# Interface_Section.net
KiCad netlist of a schematic drawn in Altium Designer
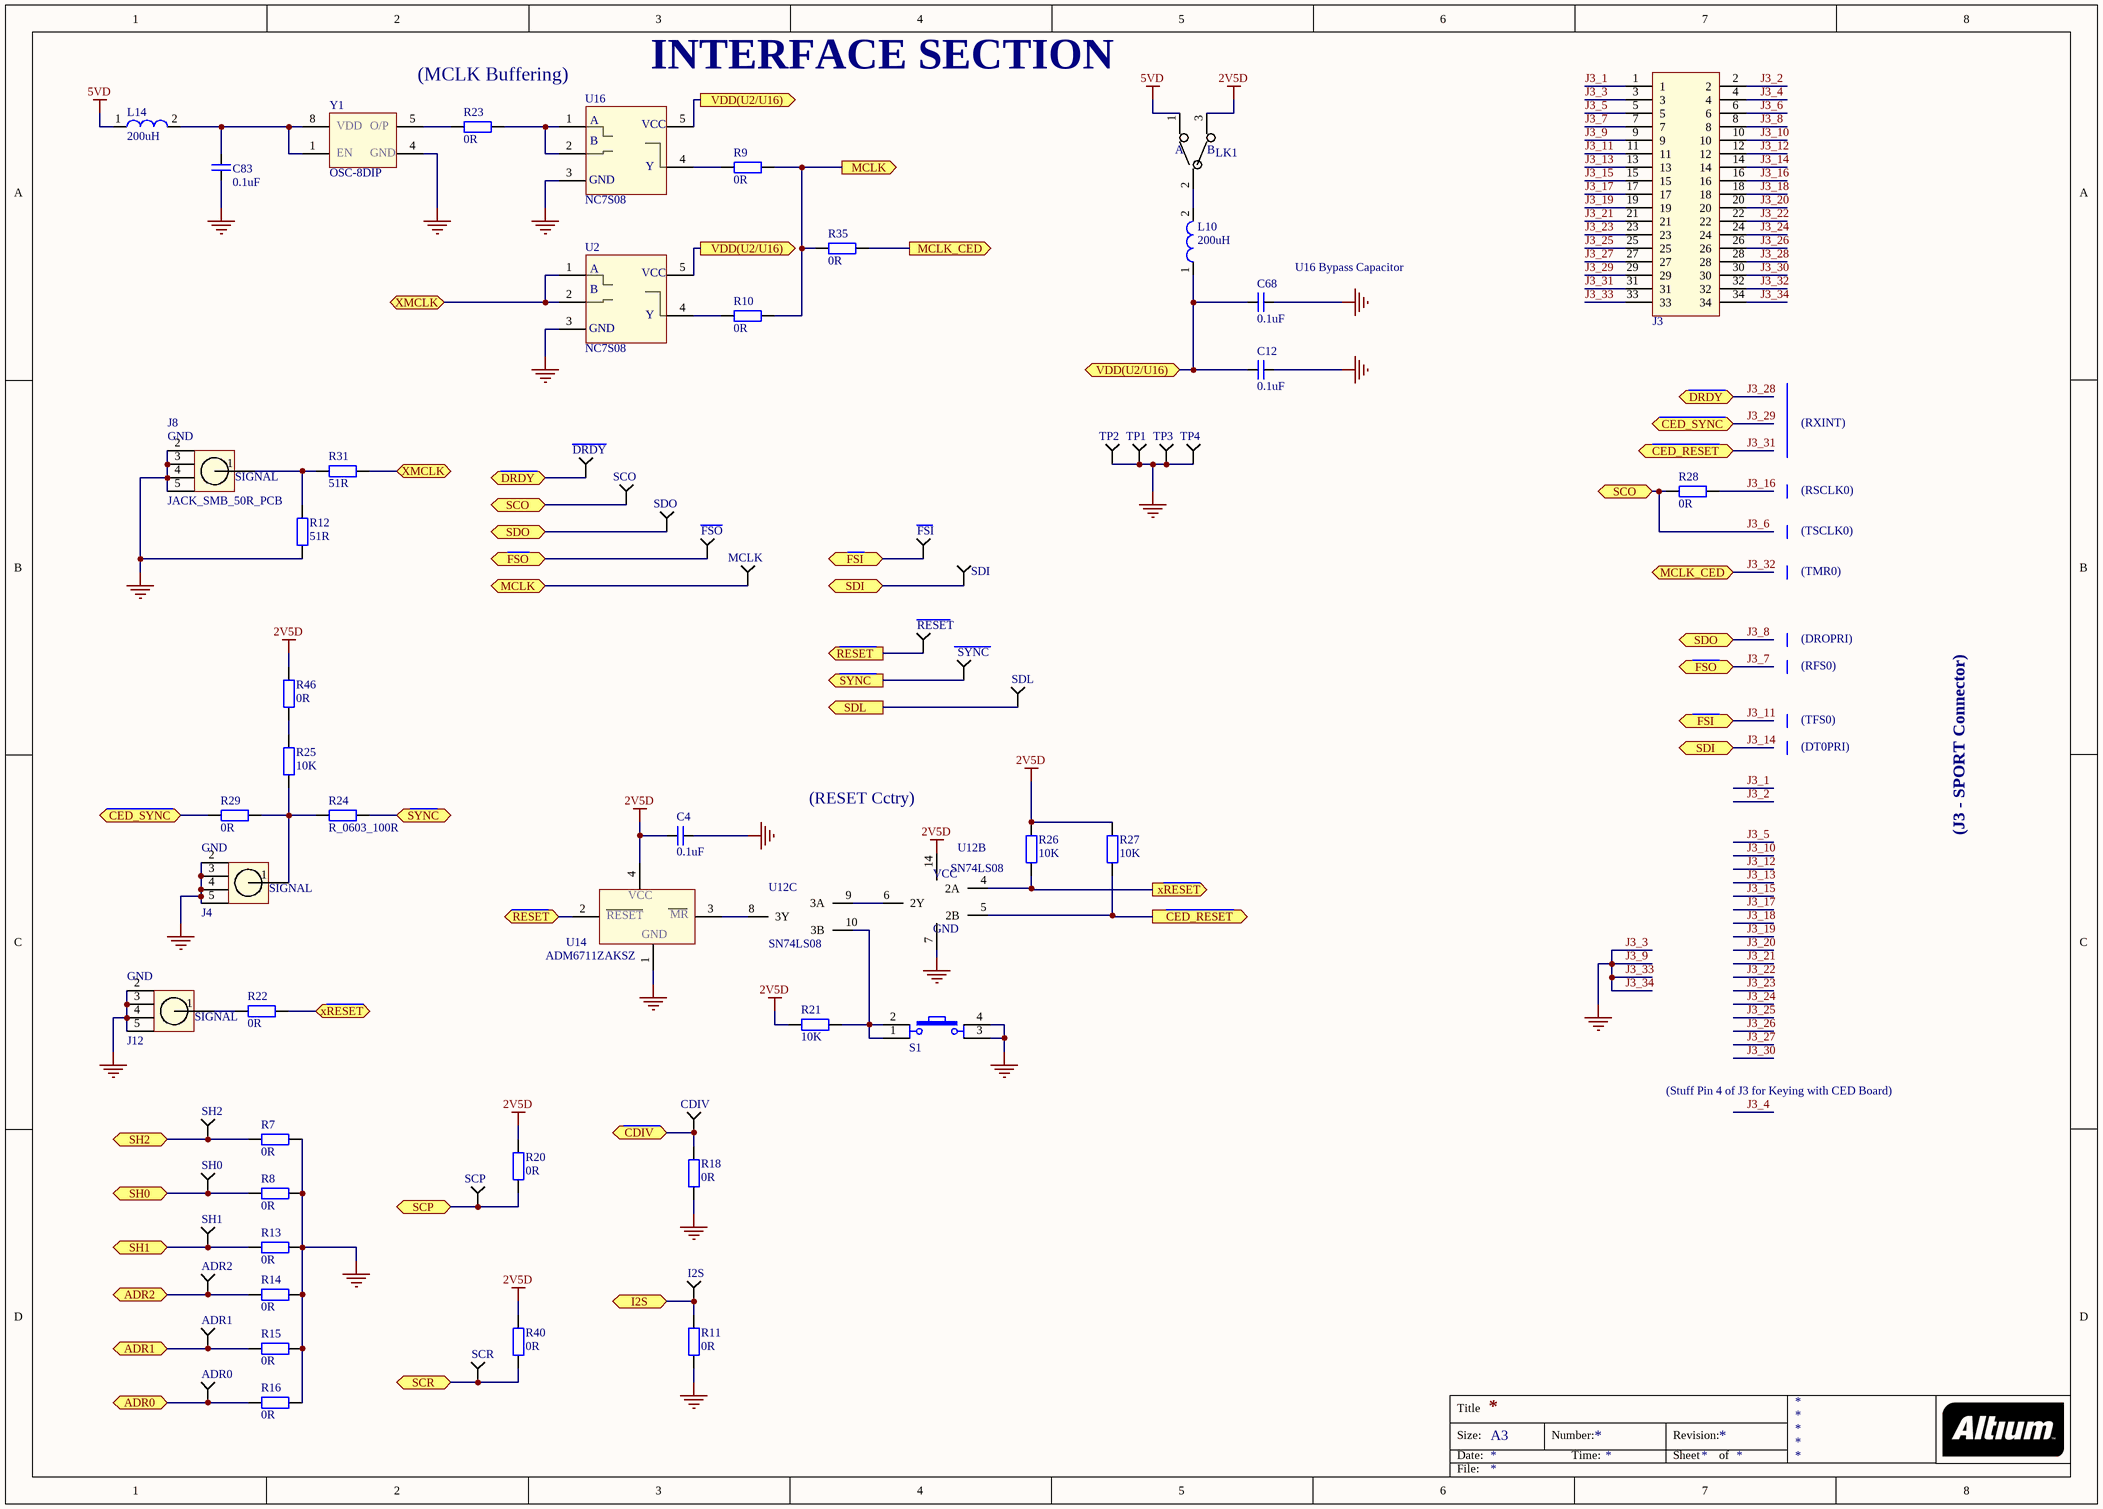
[diagram p0: Interface Section.SchDoc]

(export (version "E")
  (design (tool "Eeschema 10.0.6"))
  (components
    (comp (ref "ADR0")
      (value "Test point")
      (footprint "Test Point")
      (description "CONN HEADER VERT .100 1POS 30AU")
      (fields
        (field (name "MANUFACTURER") "TE Connectivity AMP Connectors")
        (field (name "MANUFACTURER PART NUMBER") "87220-1")
      )
      (libsource (lib "AD7763EDZ_Schematics Library") (part "Testpoint_PIN"))
    )
    (comp (ref "ADR1")
      (value "Test point")
      (footprint "Test Point")
      (description "CONN HEADER VERT .100 1POS 30AU")
      (fields
        (field (name "MANUFACTURER") "TE Connectivity AMP Connectors")
        (field (name "MANUFACTURER PART NUMBER") "87220-1")
      )
      (libsource (lib "AD7763EDZ_Schematics Library") (part "Testpoint_PIN"))
    )
    (comp (ref "ADR2")
      (value "Test point")
      (footprint "Test Point")
      (description "CONN HEADER VERT .100 1POS 30AU")
      (fields
        (field (name "MANUFACTURER") "TE Connectivity AMP Connectors")
        (field (name "MANUFACTURER PART NUMBER") "87220-1")
      )
      (libsource (lib "AD7763EDZ_Schematics Library") (part "Testpoint_PIN"))
    )
    (comp (ref "C4")
      (value "0.1uF")
      (footprint "C0603")
      (description "Ceramic Capacitor, 0.1 µF, ± 10%, X7R, 16 V, 0603")
      (fields
        (field (name "MANUFACTURER") "MULTICOMP")
        (field (name "MANUFACTURER PART NUMBER") "MCB0603R104KCT")
      )
      (libsource (lib "AD7763EDZ_Schematics Library") (part "C_0603_0.1uF"))
    )
    (comp (ref "C12")
      (value "0.1uF")
      (footprint "C0603")
      (description "Ceramic Capacitor, 0.1 µF, ± 10%, X7R, 16 V, 0603")
      (fields
        (field (name "MANUFACTURER") "MULTICOMP")
        (field (name "MANUFACTURER PART NUMBER") "MCB0603R104KCT")
      )
      (libsource (lib "AD7763EDZ_Schematics Library") (part "C_0603_0.1uF"))
    )
    (comp (ref "C68")
      (value "0.1uF")
      (footprint "C0603")
      (description "Ceramic Capacitor, 0.1 µF, ± 10%, X7R, 16 V, 0603")
      (fields
        (field (name "MANUFACTURER") "MULTICOMP")
        (field (name "MANUFACTURER PART NUMBER") "MCB0603R104KCT")
      )
      (libsource (lib "AD7763EDZ_Schematics Library") (part "C_0603_0.1uF"))
    )
    (comp (ref "C83")
      (value "0.1uF")
      (footprint "C0603")
      (description "Ceramic Capacitor, 0.1 µF, ± 10%, X7R, 16 V, 0603")
      (fields
        (field (name "MANUFACTURER") "MULTICOMP")
        (field (name "MANUFACTURER PART NUMBER") "MCB0603R104KCT")
      )
      (libsource (lib "AD7763EDZ_Schematics Library") (part "C_0603_0.1uF"))
    )
    (comp (ref "CDIV")
      (value "Test point")
      (footprint "Test Point")
      (description "CONN HEADER VERT .100 1POS 30AU")
      (fields
        (field (name "MANUFACTURER") "TE Connectivity AMP Connectors")
        (field (name "MANUFACTURER PART NUMBER") "87220-1")
      )
      (libsource (lib "AD7763EDZ_Schematics Library") (part "Testpoint_PIN"))
    )
    (comp (ref "DRDY")
      (value "Test point")
      (footprint "Test Point")
      (description "CONN HEADER VERT .100 1POS 30AU")
      (fields
        (field (name "MANUFACTURER") "TE Connectivity AMP Connectors")
        (field (name "MANUFACTURER PART NUMBER") "87220-1")
      )
      (libsource (lib "AD7763EDZ_Schematics Library") (part "Testpoint_PIN"))
    )
    (comp (ref "FSI")
      (value "Test point")
      (footprint "Test Point")
      (description "CONN HEADER VERT .100 1POS 30AU")
      (fields
        (field (name "MANUFACTURER") "TE Connectivity AMP Connectors")
        (field (name "MANUFACTURER PART NUMBER") "87220-1")
      )
      (libsource (lib "AD7763EDZ_Schematics Library") (part "Testpoint_PIN"))
    )
    (comp (ref "FSO")
      (value "Test point")
      (footprint "Test Point")
      (description "CONN HEADER VERT .100 1POS 30AU")
      (fields
        (field (name "MANUFACTURER") "TE Connectivity AMP Connectors")
        (field (name "MANUFACTURER PART NUMBER") "87220-1")
      )
      (libsource (lib "AD7763EDZ_Schematics Library") (part "Testpoint_PIN"))
    )
    (comp (ref "I2S")
      (value "Test point")
      (footprint "Test Point")
      (description "CONN HEADER VERT .100 1POS 30AU")
      (fields
        (field (name "MANUFACTURER") "TE Connectivity AMP Connectors")
        (field (name "MANUFACTURER PART NUMBER") "87220-1")
      )
      (libsource (lib "AD7763EDZ_Schematics Library") (part "Testpoint_PIN"))
    )
    (comp (ref "J3")
      (value "Female Header 17x2")
      (footprint "FM_Header_17x2_Bottom")
      (description "34pin 2.54mm DIL Vertical PC Tail Socket")
      (fields (field (name "MANUFACTURER") "Harwin") (field (name "MANUFACTURER PART NUMBER") "M20-7831746"))
      (libsource (lib "AD7763EDZ_Schematics Library") (part "Female header 17x2"))
    )
    (comp (ref "J4")
      (value "JACK_SMB_50R_PCB")
      (footprint "SMB Jack Radial")
      (description "CONN SMB JACK STR 50 OHM PCB")
      (fields (field (name "MANUFACTURER") "RADIALL") (field (name "MANUFACTURER PART NUMBER") "R114426000"))
      (libsource (lib "AD7763EDZ_Schematics Library") (part "JACK_SMB_50R_PCB"))
    )
    (comp (ref "J8")
      (value "JACK_SMB_50R_PCB")
      (footprint "SMB Jack Radial")
      (description "CONN SMB JACK STR 50 OHM PCB")
      (fields (field (name "MANUFACTURER") "RADIALL") (field (name "MANUFACTURER PART NUMBER") "R114426000"))
      (libsource (lib "AD7763EDZ_Schematics Library") (part "JACK_SMB_50R_PCB"))
    )
    (comp (ref "J12")
      (value "JACK_SMB_50R_PCB")
      (footprint "SMB Jack Radial")
      (description "CONN SMB JACK STR 50 OHM PCB")
      (fields (field (name "MANUFACTURER") "RADIALL") (field (name "MANUFACTURER PART NUMBER") "R114426000"))
      (libsource (lib "AD7763EDZ_Schematics Library") (part "JACK_SMB_50R_PCB"))
    )
    (comp (ref "L10")
      (value "200uH")
      (footprint "IND_0603")
      (description "FERRITE BEAD 1000 OHM 0.2A 0603")
      (fields
        (field (name "MANUFACTURER") "Wurth Electronics Inc")
        (field (name "MANUFACTURER PART NUMBER") "74279266")
      )
      (libsource (lib "AD7763EDZ_Schematics Library") (part "FERRITE_BEAT_200uH"))
    )
    (comp (ref "L14")
      (value "200uH")
      (footprint "IND_0603")
      (description "FERRITE BEAD 1000 OHM 0.2A 0603")
      (fields
        (field (name "MANUFACTURER") "Wurth Electronics Inc")
        (field (name "MANUFACTURER PART NUMBER") "74279266")
      )
      (libsource (lib "AD7763EDZ_Schematics Library") (part "FERRITE_BEAT_200uH"))
    )
    (comp (ref "LK1")
      (value "HEADER_3PIN_SIL")
      (footprint "M_Header_3")
      (description "SIL VERTICAL PC TAIL PIN HEADER 3PIN, M20-9990345")
      (fields
        (field (name "MANUFACTURER") "Harwin Inc")
        (field (name "MANUFACTURER PART NUMBER") "M20-9990345")
      )
      (libsource (lib "AD7763EDZ_Schematics Library") (part "HEADER_3PIN_SIL"))
    )
    (comp (ref "MCLK")
      (value "Test point")
      (footprint "Test Point")
      (description "CONN HEADER VERT .100 1POS 30AU")
      (fields
        (field (name "MANUFACTURER") "TE Connectivity AMP Connectors")
        (field (name "MANUFACTURER PART NUMBER") "87220-1")
      )
      (libsource (lib "AD7763EDZ_Schematics Library") (part "Testpoint_PIN"))
    )
    (comp (ref "R7")
      (value "0R")
      (footprint "R_0603")
      (description "RES SMD 0.0 OHM JUMPER 1/16W")
      (fields
        (field (name "MANUFACTURER") "TE Connectivity AMP Connectors")
        (field (name "MANUFACTURER PART NUMBER") "6-1622826-4")
      )
      (libsource (lib "AD7763EDZ_Schematics Library") (part "R_0603_0R"))
    )
    (comp (ref "R8")
      (value "0R")
      (footprint "R_0603")
      (description "RES SMD 0.0 OHM JUMPER 1/16W")
      (fields
        (field (name "MANUFACTURER") "TE Connectivity AMP Connectors")
        (field (name "MANUFACTURER PART NUMBER") "6-1622826-4")
      )
      (libsource (lib "AD7763EDZ_Schematics Library") (part "R_0603_0R"))
    )
    (comp (ref "R9")
      (value "0R")
      (footprint "R_0603")
      (description "RES SMD 0.0 OHM JUMPER 1/16W")
      (fields
        (field (name "MANUFACTURER") "TE Connectivity AMP Connectors")
        (field (name "MANUFACTURER PART NUMBER") "6-1622826-4")
      )
      (libsource (lib "AD7763EDZ_Schematics Library") (part "R_0603_0R"))
    )
    (comp (ref "R10")
      (value "0R")
      (footprint "R_0603")
      (description "RES SMD 0.0 OHM JUMPER 1/16W")
      (fields
        (field (name "MANUFACTURER") "TE Connectivity AMP Connectors")
        (field (name "MANUFACTURER PART NUMBER") "6-1622826-4")
      )
      (libsource (lib "AD7763EDZ_Schematics Library") (part "R_0603_0R"))
    )
    (comp (ref "R11")
      (value "0R")
      (footprint "R_0603")
      (description "RES SMD 0.0 OHM JUMPER 1/16W")
      (fields
        (field (name "MANUFACTURER") "TE Connectivity AMP Connectors")
        (field (name "MANUFACTURER PART NUMBER") "6-1622826-4")
      )
      (libsource (lib "AD7763EDZ_Schematics Library") (part "R_0603_0R"))
    )
    (comp (ref "R12")
      (value "51R")
      (footprint "R_0603")
      (description "RES SMD 51 OHM 1% 1/16W 0603")
      (fields
        (field (name "MANUFACTURER") "MULTICOMP")
        (field (name "MANUFACTURER PART NUMBER") "MC0063W0603151R")
      )
      (libsource (lib "AD7763EDZ_Schematics Library") (part "R_0603_51R"))
    )
    (comp (ref "R13")
      (value "0R")
      (footprint "R_0603")
      (description "RES SMD 0.0 OHM JUMPER 1/16W")
      (fields
        (field (name "MANUFACTURER") "TE Connectivity AMP Connectors")
        (field (name "MANUFACTURER PART NUMBER") "6-1622826-4")
      )
      (libsource (lib "AD7763EDZ_Schematics Library") (part "R_0603_0R"))
    )
    (comp (ref "R14")
      (value "0R")
      (footprint "R_0603")
      (description "RES SMD 0.0 OHM JUMPER 1/16W")
      (fields
        (field (name "MANUFACTURER") "TE Connectivity AMP Connectors")
        (field (name "MANUFACTURER PART NUMBER") "6-1622826-4")
      )
      (libsource (lib "AD7763EDZ_Schematics Library") (part "R_0603_0R"))
    )
    (comp (ref "R15")
      (value "0R")
      (footprint "R_0603")
      (description "RES SMD 0.0 OHM JUMPER 1/16W")
      (fields
        (field (name "MANUFACTURER") "TE Connectivity AMP Connectors")
        (field (name "MANUFACTURER PART NUMBER") "6-1622826-4")
      )
      (libsource (lib "AD7763EDZ_Schematics Library") (part "R_0603_0R"))
    )
    (comp (ref "R16")
      (value "0R")
      (footprint "R_0603")
      (description "RES SMD 0.0 OHM JUMPER 1/16W")
      (fields
        (field (name "MANUFACTURER") "TE Connectivity AMP Connectors")
        (field (name "MANUFACTURER PART NUMBER") "6-1622826-4")
      )
      (libsource (lib "AD7763EDZ_Schematics Library") (part "R_0603_0R"))
    )
    (comp (ref "R18")
      (value "0R")
      (footprint "R_0603")
      (description "RES SMD 0.0 OHM JUMPER 1/16W")
      (fields
        (field (name "MANUFACTURER") "TE Connectivity AMP Connectors")
        (field (name "MANUFACTURER PART NUMBER") "6-1622826-4")
      )
      (libsource (lib "AD7763EDZ_Schematics Library") (part "R_0603_0R"))
    )
    (comp (ref "R20")
      (value "0R")
      (footprint "R_0603")
      (description "RES SMD 0.0 OHM JUMPER 1/16W")
      (fields
        (field (name "MANUFACTURER") "TE Connectivity AMP Connectors")
        (field (name "MANUFACTURER PART NUMBER") "6-1622826-4")
      )
      (libsource (lib "AD7763EDZ_Schematics Library") (part "R_0603_0R"))
    )
    (comp (ref "R21")
      (value "10K")
      (footprint "R_0603")
      (description "RES SMD 10K OHM 1% 1/16W 0603")
      (fields
        (field (name "MANUFACTURER") "MULTICOMP")
        (field (name "MANUFACTURER PART NUMBER") "MC0063W0603110K")
      )
      (libsource (lib "AD7763EDZ_Schematics Library") (part "R_0603_10K"))
    )
    (comp (ref "R22")
      (value "0R")
      (footprint "R_0603")
      (description "RES SMD 0.0 OHM JUMPER 1/16W")
      (fields
        (field (name "MANUFACTURER") "TE Connectivity AMP Connectors")
        (field (name "MANUFACTURER PART NUMBER") "6-1622826-4")
      )
      (libsource (lib "AD7763EDZ_Schematics Library") (part "R_0603_0R"))
    )
    (comp (ref "R23")
      (value "0R")
      (footprint "R_0603")
      (description "RES SMD 0.0 OHM JUMPER 1/16W")
      (fields
        (field (name "MANUFACTURER") "TE Connectivity AMP Connectors")
        (field (name "MANUFACTURER PART NUMBER") "6-1622826-4")
      )
      (libsource (lib "AD7763EDZ_Schematics Library") (part "R_0603_0R"))
    )
    (comp (ref "R24")
      (value "R_0603_100R")
      (footprint "R_0603")
      (description "RES SMD 100 OHM 1% 1/10W 0603")
      (fields
        (field (name "MANUFACTURER") "Yageo")
        (field (name "MANUFACTURER PART NUMBER") "RC0603FR-07100RL")
      )
      (libsource (lib "AD7763") (part "R_0603_100R"))
    )
    (comp (ref "R25")
      (value "10K")
      (footprint "R_0603")
      (description "RES SMD 10K OHM 1% 1/16W 0603")
      (fields
        (field (name "MANUFACTURER") "MULTICOMP")
        (field (name "MANUFACTURER PART NUMBER") "MC0063W0603110K")
      )
      (libsource (lib "AD7763EDZ_Schematics Library") (part "R_0603_10K"))
    )
    (comp (ref "R26")
      (value "10K")
      (footprint "R_0603")
      (description "RES SMD 10K OHM 1% 1/16W 0603")
      (fields
        (field (name "MANUFACTURER") "MULTICOMP")
        (field (name "MANUFACTURER PART NUMBER") "MC0063W0603110K")
      )
      (libsource (lib "AD7763EDZ_Schematics Library") (part "R_0603_10K"))
    )
    (comp (ref "R27")
      (value "10K")
      (footprint "R_0603")
      (description "RES SMD 10K OHM 1% 1/16W 0603")
      (fields
        (field (name "MANUFACTURER") "MULTICOMP")
        (field (name "MANUFACTURER PART NUMBER") "MC0063W0603110K")
      )
      (libsource (lib "AD7763EDZ_Schematics Library") (part "R_0603_10K"))
    )
    (comp (ref "R28")
      (value "0R")
      (footprint "R_0603")
      (description "RES SMD 0.0 OHM JUMPER 1/16W")
      (fields
        (field (name "MANUFACTURER") "TE Connectivity AMP Connectors")
        (field (name "MANUFACTURER PART NUMBER") "6-1622826-4")
      )
      (libsource (lib "AD7763EDZ_Schematics Library") (part "R_0603_0R"))
    )
    (comp (ref "R29")
      (value "0R")
      (footprint "R_0603")
      (description "RES SMD 0.0 OHM JUMPER 1/16W")
      (fields
        (field (name "MANUFACTURER") "TE Connectivity AMP Connectors")
        (field (name "MANUFACTURER PART NUMBER") "6-1622826-4")
      )
      (libsource (lib "AD7763EDZ_Schematics Library") (part "R_0603_0R"))
    )
    (comp (ref "R31")
      (value "51R")
      (footprint "R_0603")
      (description "RES SMD 51 OHM 1% 1/16W 0603")
      (fields
        (field (name "MANUFACTURER") "MULTICOMP")
        (field (name "MANUFACTURER PART NUMBER") "MC0063W0603151R")
      )
      (libsource (lib "AD7763EDZ_Schematics Library") (part "R_0603_51R"))
    )
    (comp (ref "R35")
      (value "0R")
      (footprint "R_0603")
      (description "RES SMD 0.0 OHM JUMPER 1/16W")
      (fields
        (field (name "MANUFACTURER") "TE Connectivity AMP Connectors")
        (field (name "MANUFACTURER PART NUMBER") "6-1622826-4")
      )
      (libsource (lib "AD7763EDZ_Schematics Library") (part "R_0603_0R"))
    )
    (comp (ref "R40")
      (value "0R")
      (footprint "R_0603")
      (description "RES SMD 0.0 OHM JUMPER 1/16W")
      (fields
        (field (name "MANUFACTURER") "TE Connectivity AMP Connectors")
        (field (name "MANUFACTURER PART NUMBER") "6-1622826-4")
      )
      (libsource (lib "AD7763EDZ_Schematics Library") (part "R_0603_0R"))
    )
    (comp (ref "R46")
      (value "0R")
      (footprint "R_0603")
      (description "RES SMD 0.0 OHM JUMPER 1/16W")
      (fields
        (field (name "MANUFACTURER") "TE Connectivity AMP Connectors")
        (field (name "MANUFACTURER PART NUMBER") "6-1622826-4")
      )
      (libsource (lib "AD7763EDZ_Schematics Library") (part "R_0603_0R"))
    )
    (comp (ref "RESET")
      (value "Test point")
      (footprint "Test Point")
      (description "CONN HEADER VERT .100 1POS 30AU")
      (fields
        (field (name "MANUFACTURER") "TE Connectivity AMP Connectors")
        (field (name "MANUFACTURER PART NUMBER") "87220-1")
      )
      (libsource (lib "AD7763EDZ_Schematics Library") (part "Testpoint_PIN"))
    )
    (comp (ref "S1")
      (value "B3S-1000")
      (footprint "B3S-1000")
      (description "SWITCH TACTILE SPST-NO 0.05A 24V")
      (fields (field (name "MANUFACTURER") "Omron Electronics Inc-EMC Div"))
      (libsource (lib "AD7763EDZ_Schematics Library") (part "PUSH_BUTTON_SWITCH"))
    )
    (comp (ref "SCO")
      (value "Test point")
      (footprint "Test Point")
      (description "CONN HEADER VERT .100 1POS 30AU")
      (fields
        (field (name "MANUFACTURER") "TE Connectivity AMP Connectors")
        (field (name "MANUFACTURER PART NUMBER") "87220-1")
      )
      (libsource (lib "AD7763EDZ_Schematics Library") (part "Testpoint_PIN"))
    )
    (comp (ref "SCP")
      (value "Test point")
      (footprint "Test Point")
      (description "CONN HEADER VERT .100 1POS 30AU")
      (fields
        (field (name "MANUFACTURER") "TE Connectivity AMP Connectors")
        (field (name "MANUFACTURER PART NUMBER") "87220-1")
      )
      (libsource (lib "AD7763EDZ_Schematics Library") (part "Testpoint_PIN"))
    )
    (comp (ref "SCR")
      (value "Test point")
      (footprint "Test Point")
      (description "CONN HEADER VERT .100 1POS 30AU")
      (fields
        (field (name "MANUFACTURER") "TE Connectivity AMP Connectors")
        (field (name "MANUFACTURER PART NUMBER") "87220-1")
      )
      (libsource (lib "AD7763EDZ_Schematics Library") (part "Testpoint_PIN"))
    )
    (comp (ref "SDI")
      (value "Test point")
      (footprint "Test Point")
      (description "CONN HEADER VERT .100 1POS 30AU")
      (fields
        (field (name "MANUFACTURER") "TE Connectivity AMP Connectors")
        (field (name "MANUFACTURER PART NUMBER") "87220-1")
      )
      (libsource (lib "AD7763EDZ_Schematics Library") (part "Testpoint_PIN"))
    )
    (comp (ref "SDL")
      (value "Test point")
      (footprint "Test Point")
      (description "CONN HEADER VERT .100 1POS 30AU")
      (fields
        (field (name "MANUFACTURER") "TE Connectivity AMP Connectors")
        (field (name "MANUFACTURER PART NUMBER") "87220-1")
      )
      (libsource (lib "AD7763EDZ_Schematics Library") (part "Testpoint_PIN"))
    )
    (comp (ref "SDO")
      (value "Test point")
      (footprint "Test Point")
      (description "CONN HEADER VERT .100 1POS 30AU")
      (fields
        (field (name "MANUFACTURER") "TE Connectivity AMP Connectors")
        (field (name "MANUFACTURER PART NUMBER") "87220-1")
      )
      (libsource (lib "AD7763EDZ_Schematics Library") (part "Testpoint_PIN"))
    )
    (comp (ref "SH0")
      (value "Test point")
      (footprint "Test Point")
      (description "CONN HEADER VERT .100 1POS 30AU")
      (fields
        (field (name "MANUFACTURER") "TE Connectivity AMP Connectors")
        (field (name "MANUFACTURER PART NUMBER") "87220-1")
      )
      (libsource (lib "AD7763EDZ_Schematics Library") (part "Testpoint_PIN"))
    )
    (comp (ref "SH1")
      (value "Test point")
      (footprint "Test Point")
      (description "CONN HEADER VERT .100 1POS 30AU")
      (fields
        (field (name "MANUFACTURER") "TE Connectivity AMP Connectors")
        (field (name "MANUFACTURER PART NUMBER") "87220-1")
      )
      (libsource (lib "AD7763EDZ_Schematics Library") (part "Testpoint_PIN"))
    )
    (comp (ref "SH2")
      (value "Test point")
      (footprint "Test Point")
      (description "CONN HEADER VERT .100 1POS 30AU")
      (fields
        (field (name "MANUFACTURER") "TE Connectivity AMP Connectors")
        (field (name "MANUFACTURER PART NUMBER") "87220-1")
      )
      (libsource (lib "AD7763EDZ_Schematics Library") (part "Testpoint_PIN"))
    )
    (comp (ref "SYNC")
      (value "Test point")
      (footprint "Test Point")
      (description "CONN HEADER VERT .100 1POS 30AU")
      (fields
        (field (name "MANUFACTURER") "TE Connectivity AMP Connectors")
        (field (name "MANUFACTURER PART NUMBER") "87220-1")
      )
      (libsource (lib "AD7763EDZ_Schematics Library") (part "Testpoint_PIN"))
    )
    (comp (ref "TP1")
      (value "Test point")
      (footprint "Test Point")
      (description "CONN HEADER VERT .100 1POS 30AU")
      (fields
        (field (name "MANUFACTURER") "TE Connectivity AMP Connectors")
        (field (name "MANUFACTURER PART NUMBER") "87220-1")
      )
      (libsource (lib "AD7763EDZ_Schematics Library") (part "Testpoint_PIN"))
    )
    (comp (ref "TP2")
      (value "Test point")
      (footprint "Test Point")
      (description "CONN HEADER VERT .100 1POS 30AU")
      (fields
        (field (name "MANUFACTURER") "TE Connectivity AMP Connectors")
        (field (name "MANUFACTURER PART NUMBER") "87220-1")
      )
      (libsource (lib "AD7763EDZ_Schematics Library") (part "Testpoint_PIN"))
    )
    (comp (ref "TP3")
      (value "Test point")
      (footprint "Test Point")
      (description "CONN HEADER VERT .100 1POS 30AU")
      (fields
        (field (name "MANUFACTURER") "TE Connectivity AMP Connectors")
        (field (name "MANUFACTURER PART NUMBER") "87220-1")
      )
      (libsource (lib "AD7763EDZ_Schematics Library") (part "Testpoint_PIN"))
    )
    (comp (ref "TP4")
      (value "Test point")
      (footprint "Test Point")
      (description "CONN HEADER VERT .100 1POS 30AU")
      (fields
        (field (name "MANUFACTURER") "TE Connectivity AMP Connectors")
        (field (name "MANUFACTURER PART NUMBER") "87220-1")
      )
      (libsource (lib "AD7763EDZ_Schematics Library") (part "Testpoint_PIN"))
    )
    (comp (ref "U2")
      (value "NC7S08")
      (footprint "SOT23-5")
      (description "IC GATE AND 1CH 2-INP SOT-23-5")
      (fields
        (field (name "MANUFACTURER") "Fairchild Semiconductor")
        (field (name "MANUFACTURER PART NUMBER") "NC7SZ08M5")
      )
      (libsource (lib "AD7763EDZ_Schematics Library") (part "NC7S08"))
    )
    (comp (ref "U12")
      (value "SN74LS08")
      (footprint "TSSOP-14")
      (description "IC GATE AND 4CH 2-INP 14-TSSOP")
      (fields
        (field (name "MANUFACTURER") "Texas Instruments")
        (field (name "MANUFACTURER PART NUMBER") "SN74LVC08APWR")
      )
      (libsource (lib "AD7763") (part "74LS08"))
    )
    (comp (ref "U14")
      (value "ADM6711ZAKSZ")
      (footprint "SC70-4")
      (description "IC SUPERVISOR MPU 2.32V SC70-4")
      (fields
        (field (name "MANUFACTURER") "Analog Devices Inc")
        (field (name "MANUFACTURER PART NUMBER") "ADM6711ZAKSZ-REEL7")
      )
      (libsource (lib "AD7763EDZ_Schematics Library") (part "ADM6711"))
    )
    (comp (ref "U16")
      (value "NC7S08")
      (footprint "SOT23-5")
      (description "IC GATE AND 1CH 2-INP SOT-23-5")
      (fields
        (field (name "MANUFACTURER") "Fairchild Semiconductor")
        (field (name "MANUFACTURER PART NUMBER") "NC7SZ08M5")
      )
      (libsource (lib "AD7763EDZ_Schematics Library") (part "NC7S08"))
    )
    (comp (ref "Y1")
      (value "OSC-8DIP")
      (footprint "MXO45HS40M")
      (description "OSC XO 40.000MHZ HCMOS TTL PIN")
      (fields
        (field (name "MANUFACTURER") "CTS-Frequency Controls")
        (field (name "MANUFACTURER PART NUMBER") "MXO45HS-2C-40M0000")
      )
      (libsource (lib "AD7763EDZ_Schematics Library") (part "OSC-8DIP"))
    )
  )
  (nets
    (net (code "1") (name "/ADR0") (class "Default")
      (node (ref "ADR0") (pin "1") (pinfunction "1_1") (pintype "passive"))
      (node (ref "R16") (pin "1") (pinfunction "1_1") (pintype "passive"))
    )
    (net (code "2") (name "/ADR1") (class "Default")
      (node (ref "ADR1") (pin "1") (pinfunction "1_1") (pintype "passive"))
      (node (ref "R15") (pin "1") (pinfunction "1_1") (pintype "passive"))
    )
    (net (code "3") (name "/ADR2") (class "Default")
      (node (ref "ADR2") (pin "1") (pinfunction "1_1") (pintype "passive"))
      (node (ref "R14") (pin "1") (pinfunction "1_1") (pintype "passive"))
    )
    (net (code "4") (name "/CDIV") (class "Default")
      (node (ref "CDIV") (pin "1") (pinfunction "1_1") (pintype "passive"))
      (node (ref "R18") (pin "2") (pinfunction "2_2") (pintype "passive"))
    )
    (net (code "5") (name "/I2S") (class "Default")
      (node (ref "I2S") (pin "1") (pinfunction "1_1") (pintype "passive"))
      (node (ref "R11") (pin "2") (pinfunction "2_2") (pintype "passive"))
    )
    (net (code "6") (name "/J3_1") (class "Default")
      (node (ref "J3") (pin "1") (pinfunction "1_1") (pintype "passive"))
    )
    (net (code "7") (name "/J3_2") (class "Default")
      (node (ref "J3") (pin "2") (pinfunction "2_2") (pintype "passive"))
    )
    (net (code "8") (name "/J3_4") (class "Default")
      (node (ref "J3") (pin "4") (pinfunction "4_4") (pintype "passive"))
    )
    (net (code "9") (name "/J3_5") (class "Default")
      (node (ref "J3") (pin "5") (pinfunction "5_5") (pintype "passive"))
    )
    (net (code "10") (name "/J3_6") (class "Default")
      (node (ref "J3") (pin "6") (pinfunction "6_6") (pintype "passive"))
      (node (ref "R28") (pin "1") (pinfunction "1_1") (pintype "passive"))
      (node (ref "SCO") (pin "1") (pinfunction "1_1") (pintype "passive"))
    )
    (net (code "11") (name "/J3_7") (class "Default")
      (node (ref "FSO") (pin "1") (pinfunction "1_1") (pintype "passive"))
      (node (ref "J3") (pin "7") (pinfunction "7_7") (pintype "passive"))
    )
    (net (code "12") (name "/J3_8") (class "Default")
      (node (ref "J3") (pin "8") (pinfunction "8_8") (pintype "passive"))
      (node (ref "SDO") (pin "1") (pinfunction "1_1") (pintype "passive"))
    )
    (net (code "13") (name "/J3_10") (class "Default")
      (node (ref "J3") (pin "10") (pinfunction "10_10") (pintype "passive"))
    )
    (net (code "14") (name "/J3_11") (class "Default")
      (node (ref "FSI") (pin "1") (pinfunction "1_1") (pintype "passive"))
      (node (ref "J3") (pin "11") (pinfunction "11_11") (pintype "passive"))
    )
    (net (code "15") (name "/J3_12") (class "Default")
      (node (ref "J3") (pin "12") (pinfunction "12_12") (pintype "passive"))
    )
    (net (code "16") (name "/J3_13") (class "Default")
      (node (ref "J3") (pin "13") (pinfunction "13_13") (pintype "passive"))
    )
    (net (code "17") (name "/J3_14") (class "Default")
      (node (ref "J3") (pin "14") (pinfunction "14_14") (pintype "passive"))
      (node (ref "SDI") (pin "1") (pinfunction "1_1") (pintype "passive"))
    )
    (net (code "18") (name "/J3_15") (class "Default")
      (node (ref "J3") (pin "15") (pinfunction "15_15") (pintype "passive"))
    )
    (net (code "19") (name "/J3_16") (class "Default")
      (node (ref "J3") (pin "16") (pinfunction "16_16") (pintype "passive"))
      (node (ref "R28") (pin "2") (pinfunction "2_2") (pintype "passive"))
    )
    (net (code "20") (name "/J3_17") (class "Default")
      (node (ref "J3") (pin "17") (pinfunction "17_17") (pintype "passive"))
    )
    (net (code "21") (name "/J3_18") (class "Default")
      (node (ref "J3") (pin "18") (pinfunction "18_18") (pintype "passive"))
    )
    (net (code "22") (name "/J3_19") (class "Default")
      (node (ref "J3") (pin "19") (pinfunction "19_19") (pintype "passive"))
    )
    (net (code "23") (name "/J3_20") (class "Default")
      (node (ref "J3") (pin "20") (pinfunction "20_20") (pintype "passive"))
    )
    (net (code "24") (name "/J3_21") (class "Default")
      (node (ref "J3") (pin "21") (pinfunction "21_21") (pintype "passive"))
    )
    (net (code "25") (name "/J3_22") (class "Default")
      (node (ref "J3") (pin "22") (pinfunction "22_22") (pintype "passive"))
    )
    (net (code "26") (name "/J3_23") (class "Default")
      (node (ref "J3") (pin "23") (pinfunction "23_23") (pintype "passive"))
    )
    (net (code "27") (name "/J3_24") (class "Default")
      (node (ref "J3") (pin "24") (pinfunction "24_24") (pintype "passive"))
    )
    (net (code "28") (name "/J3_25") (class "Default")
      (node (ref "J3") (pin "25") (pinfunction "25_25") (pintype "passive"))
    )
    (net (code "29") (name "/J3_26") (class "Default")
      (node (ref "J3") (pin "26") (pinfunction "26_26") (pintype "passive"))
    )
    (net (code "30") (name "/J3_27") (class "Default")
      (node (ref "J3") (pin "27") (pinfunction "27_27") (pintype "passive"))
    )
    (net (code "31") (name "/J3_28") (class "Default")
      (node (ref "DRDY") (pin "1") (pinfunction "1_1") (pintype "passive"))
      (node (ref "J3") (pin "28") (pinfunction "28_28") (pintype "passive"))
    )
    (net (code "32") (name "/J3_29") (class "Default")
      (node (ref "J3") (pin "29") (pinfunction "29_29") (pintype "passive"))
      (node (ref "R29") (pin "2") (pinfunction "2_2") (pintype "passive"))
    )
    (net (code "33") (name "/J3_30") (class "Default")
      (node (ref "J3") (pin "30") (pinfunction "30_30") (pintype "passive"))
    )
    (net (code "34") (name "/J3_31") (class "Default")
      (node (ref "J3") (pin "31") (pinfunction "31_31") (pintype "passive"))
      (node (ref "R27") (pin "1") (pinfunction "1_1") (pintype "passive"))
      (node (ref "U12") (pin "5") (pinfunction "2B_5") (pintype "passive"))
    )
    (net (code "35") (name "/J3_32") (class "Default")
      (node (ref "J3") (pin "32") (pinfunction "32_32") (pintype "passive"))
      (node (ref "R35") (pin "2") (pinfunction "2_2") (pintype "passive"))
    )
    (net (code "36") (name "/MCLK") (class "Default")
      (node (ref "MCLK") (pin "1") (pinfunction "1_1") (pintype "passive"))
      (node (ref "R10") (pin "2") (pinfunction "2_2") (pintype "passive"))
      (node (ref "R35") (pin "1") (pinfunction "1_1") (pintype "passive"))
      (node (ref "R9") (pin "2") (pinfunction "2_2") (pintype "passive"))
    )
    (net (code "37") (name "/RESET") (class "Default")
      (node (ref "RESET") (pin "1") (pinfunction "1_1") (pintype "passive"))
      (node (ref "U14") (pin "2") (pinfunction "RESET_2") (pintype "passive"))
    )
    (net (code "38") (name "/SCP") (class "Default")
      (node (ref "R20") (pin "1") (pinfunction "1_1") (pintype "passive"))
      (node (ref "SCP") (pin "1") (pinfunction "1_1") (pintype "passive"))
    )
    (net (code "39") (name "/SCR") (class "Default")
      (node (ref "R40") (pin "1") (pinfunction "1_1") (pintype "passive"))
      (node (ref "SCR") (pin "1") (pinfunction "1_1") (pintype "passive"))
    )
    (net (code "40") (name "/SDL") (class "Default")
      (node (ref "SDL") (pin "1") (pinfunction "1_1") (pintype "passive"))
    )
    (net (code "41") (name "/SH0") (class "Default")
      (node (ref "R8") (pin "1") (pinfunction "1_1") (pintype "passive"))
      (node (ref "SH0") (pin "1") (pinfunction "1_1") (pintype "passive"))
    )
    (net (code "42") (name "/SH1") (class "Default")
      (node (ref "R13") (pin "1") (pinfunction "1_1") (pintype "passive"))
      (node (ref "SH1") (pin "1") (pinfunction "1_1") (pintype "passive"))
    )
    (net (code "43") (name "/SH2") (class "Default")
      (node (ref "R7") (pin "1") (pinfunction "1_1") (pintype "passive"))
      (node (ref "SH2") (pin "1") (pinfunction "1_1") (pintype "passive"))
    )
    (net (code "44") (name "/SYNC") (class "Default")
      (node (ref "R24") (pin "2") (pinfunction "2_2") (pintype "passive"))
      (node (ref "SYNC") (pin "1") (pinfunction "1_1") (pintype "passive"))
    )
    (net (code "45") (name "/VDD(U2{slash}U16)") (class "Default")
      (node (ref "C12") (pin "1") (pinfunction "1_1") (pintype "passive"))
      (node (ref "C68") (pin "1") (pinfunction "1_1") (pintype "passive"))
      (node (ref "L10") (pin "1") (pinfunction "1_1") (pintype "passive"))
      (node (ref "U16") (pin "5") (pinfunction "VCC_5") (pintype "passive"))
      (node (ref "U2") (pin "5") (pinfunction "VCC_5") (pintype "passive"))
    )
    (net (code "46") (name "/XMCLK") (class "Default")
      (node (ref "R31") (pin "2") (pinfunction "2_2") (pintype "passive"))
      (node (ref "U2") (pin "1") (pinfunction "A_1") (pintype "passive"))
      (node (ref "U2") (pin "2") (pinfunction "B_2") (pintype "passive"))
    )
    (net (code "47") (name "/xRESET") (class "Default")
      (node (ref "R22") (pin "2") (pinfunction "2_2") (pintype "passive"))
      (node (ref "R26") (pin "1") (pinfunction "1_1") (pintype "passive"))
      (node (ref "U12") (pin "4") (pinfunction "2A_4") (pintype "passive"))
    )
    (net (code "48") (name "2V5D") (class "Default")
      (node (ref "C4") (pin "1") (pinfunction "1_1") (pintype "passive"))
      (node (ref "LK1") (pin "3") (pinfunction "3_3") (pintype "passive"))
      (node (ref "R20") (pin "2") (pinfunction "2_2") (pintype "passive"))
      (node (ref "R21") (pin "1") (pinfunction "1_1") (pintype "passive"))
      (node (ref "R26") (pin "2") (pinfunction "2_2") (pintype "passive"))
      (node (ref "R27") (pin "2") (pinfunction "2_2") (pintype "passive"))
      (node (ref "R40") (pin "2") (pinfunction "2_2") (pintype "passive"))
      (node (ref "R46") (pin "2") (pinfunction "2_2") (pintype "passive"))
      (node (ref "U12") (pin "14") (pinfunction "VCC_14") (pintype "power_in"))
      (node (ref "U14") (pin "4") (pinfunction "RESET_4") (pintype "passive"))
    )
    (net (code "49") (name "5VD") (class "Default")
      (node (ref "L14") (pin "1") (pinfunction "1_1") (pintype "passive"))
      (node (ref "LK1") (pin "1") (pinfunction "1_1") (pintype "passive"))
    )
    (net (code "50") (name "<NO NET>") (class "Default")
      (node (ref "C12") (pin "2") (pinfunction "2_2") (pintype "passive"))
      (node (ref "C4") (pin "2") (pinfunction "2_2") (pintype "passive"))
      (node (ref "C68") (pin "2") (pinfunction "2_2") (pintype "passive"))
      (node (ref "C83") (pin "1") (pinfunction "1_1") (pintype "passive"))
      (node (ref "J12") (pin "2") (pinfunction "2_2") (pintype "power_in"))
      (node (ref "J12") (pin "3") (pinfunction "3_3") (pintype "power_in"))
      (node (ref "J12") (pin "4") (pinfunction "4_4") (pintype "power_in"))
      (node (ref "J12") (pin "5") (pinfunction "5_5") (pintype "power_in"))
      (node (ref "J3") (pin "3") (pinfunction "3_3") (pintype "passive"))
      (node (ref "J3") (pin "33") (pinfunction "33_33") (pintype "passive"))
      (node (ref "J3") (pin "34") (pinfunction "34_34") (pintype "passive"))
      (node (ref "J3") (pin "9") (pinfunction "9_9") (pintype "passive"))
      (node (ref "J4") (pin "2") (pinfunction "2_2") (pintype "power_in"))
      (node (ref "J4") (pin "3") (pinfunction "3_3") (pintype "power_in"))
      (node (ref "J4") (pin "4") (pinfunction "4_4") (pintype "power_in"))
      (node (ref "J4") (pin "5") (pinfunction "5_5") (pintype "power_in"))
      (node (ref "J8") (pin "2") (pinfunction "2_2") (pintype "power_in"))
      (node (ref "J8") (pin "3") (pinfunction "3_3") (pintype "power_in"))
      (node (ref "J8") (pin "4") (pinfunction "4_4") (pintype "power_in"))
      (node (ref "J8") (pin "5") (pinfunction "5_5") (pintype "power_in"))
      (node (ref "R11") (pin "1") (pinfunction "1_1") (pintype "passive"))
      (node (ref "R12") (pin "1") (pinfunction "1_1") (pintype "passive"))
      (node (ref "R13") (pin "2") (pinfunction "2_2") (pintype "passive"))
      (node (ref "R14") (pin "2") (pinfunction "2_2") (pintype "passive"))
      (node (ref "R15") (pin "2") (pinfunction "2_2") (pintype "passive"))
      (node (ref "R16") (pin "2") (pinfunction "2_2") (pintype "passive"))
      (node (ref "R18") (pin "1") (pinfunction "1_1") (pintype "passive"))
      (node (ref "R7") (pin "2") (pinfunction "2_2") (pintype "passive"))
      (node (ref "R8") (pin "2") (pinfunction "2_2") (pintype "passive"))
      (node (ref "S1") (pin "3") (pinfunction "3_3") (pintype "passive"))
      (node (ref "S1") (pin "4") (pinfunction "4_4") (pintype "passive"))
      (node (ref "TP1") (pin "1") (pinfunction "1_1") (pintype "passive"))
      (node (ref "TP2") (pin "1") (pinfunction "1_1") (pintype "passive"))
      (node (ref "TP3") (pin "1") (pinfunction "1_1") (pintype "passive"))
      (node (ref "TP4") (pin "1") (pinfunction "1_1") (pintype "passive"))
      (node (ref "U12") (pin "7") (pinfunction "GND_7") (pintype "power_in"))
      (node (ref "U14") (pin "1") (pinfunction "GND_1") (pintype "passive"))
      (node (ref "U16") (pin "3") (pinfunction "GND_3") (pintype "passive"))
      (node (ref "U2") (pin "3") (pinfunction "GND_3") (pintype "passive"))
      (node (ref "Y1") (pin "4") (pinfunction "GND_4") (pintype "passive"))
    )
    (net (code "51") (name "Net-(J4-Pad1)") (class "Default")
      (node (ref "J4") (pin "1") (pinfunction "1_1") (pintype "passive"))
      (node (ref "R24") (pin "1") (pinfunction "1_1") (pintype "passive"))
      (node (ref "R25") (pin "1") (pinfunction "1_1") (pintype "passive"))
      (node (ref "R29") (pin "1") (pinfunction "1_1") (pintype "passive"))
    )
    (net (code "52") (name "Net-(J8-Pad1)") (class "Default")
      (node (ref "J8") (pin "1") (pinfunction "1_1") (pintype "passive"))
      (node (ref "R12") (pin "2") (pinfunction "2_2") (pintype "passive"))
      (node (ref "R31") (pin "1") (pinfunction "1_1") (pintype "passive"))
    )
    (net (code "53") (name "Net-(J12-Pad1)") (class "Default")
      (node (ref "J12") (pin "1") (pinfunction "1_1") (pintype "passive"))
      (node (ref "R22") (pin "1") (pinfunction "1_1") (pintype "passive"))
    )
    (net (code "54") (name "Net-(LK1-SEL)") (class "Default")
      (node (ref "L10") (pin "2") (pinfunction "2_2") (pintype "passive"))
      (node (ref "LK1") (pin "2") (pinfunction "SEL_2") (pintype "passive"))
    )
    (net (code "55") (name "Net-(R25-Pad2)") (class "Default")
      (node (ref "R25") (pin "2") (pinfunction "2_2") (pintype "passive"))
      (node (ref "R46") (pin "1") (pinfunction "1_1") (pintype "passive"))
    )
    (net (code "56") (name "Net-(U2-Y)") (class "Default")
      (node (ref "R10") (pin "1") (pinfunction "1_1") (pintype "passive"))
      (node (ref "U2") (pin "4") (pinfunction "Y_4") (pintype "passive"))
    )
    (net (code "57") (name "Net-(U12B-2Y)") (class "Default")
      (node (ref "U12") (pin "6") (pinfunction "2Y_6") (pintype "passive"))
      (node (ref "U12") (pin "9") (pinfunction "3A_9") (pintype "passive"))
    )
    (net (code "58") (name "Net-(U12C-3B)") (class "Default")
      (node (ref "R21") (pin "2") (pinfunction "2_2") (pintype "passive"))
      (node (ref "S1") (pin "1") (pinfunction "1_1") (pintype "passive"))
      (node (ref "S1") (pin "2") (pinfunction "2_2") (pintype "passive"))
      (node (ref "U12") (pin "10") (pinfunction "3B_10") (pintype "passive"))
    )
    (net (code "59") (name "Net-(U12C-3Y)") (class "Default")
      (node (ref "U12") (pin "8") (pinfunction "3Y_8") (pintype "passive"))
      (node (ref "U14") (pin "3") (pinfunction "MR_3") (pintype "passive"))
    )
    (net (code "60") (name "Net-(U16-A)") (class "Default")
      (node (ref "R23") (pin "2") (pinfunction "2_2") (pintype "passive"))
      (node (ref "U16") (pin "1") (pinfunction "A_1") (pintype "passive"))
      (node (ref "U16") (pin "2") (pinfunction "B_2") (pintype "passive"))
    )
    (net (code "61") (name "Net-(U16-Y)") (class "Default")
      (node (ref "R9") (pin "1") (pinfunction "1_1") (pintype "passive"))
      (node (ref "U16") (pin "4") (pinfunction "Y_4") (pintype "passive"))
    )
    (net (code "62") (name "Net-(Y1-EN)") (class "Default")
      (node (ref "C83") (pin "2") (pinfunction "2_2") (pintype "passive"))
      (node (ref "L14") (pin "2") (pinfunction "2_2") (pintype "passive"))
      (node (ref "Y1") (pin "1") (pinfunction "EN_1") (pintype "passive"))
      (node (ref "Y1") (pin "8") (pinfunction "VDD_8") (pintype "passive"))
    )
    (net (code "63") (name "Net-(Y1-O{slash}P)") (class "Default")
      (node (ref "R23") (pin "1") (pinfunction "1_1") (pintype "passive"))
      (node (ref "Y1") (pin "5") (pinfunction "O/P_5") (pintype "passive"))
    )
  )
)
